# Puls_schaltbild_1_2017.net
KiCad netlist of a schematic drawn in EAGLE
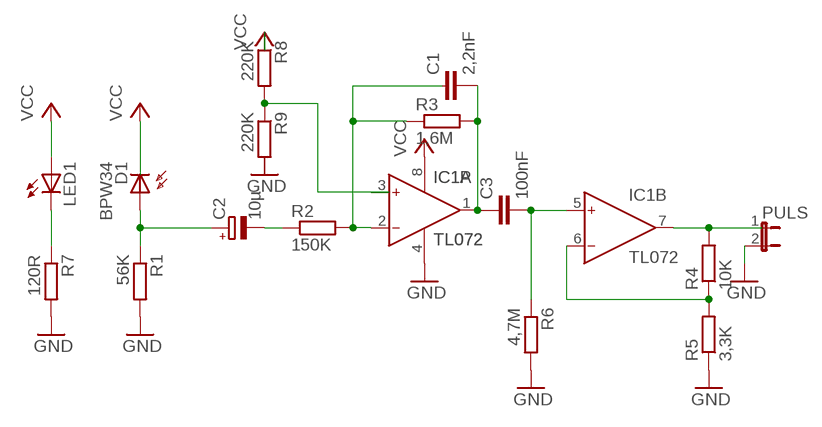
[diagram p0: schematic, sheet 1]

(export (version "E")
  (design (tool "Eeschema 10.0.6"))
  (components
    (comp (ref "C1")
      (value "2,2nF")
      (footprint "eagle-import:C050-024X044")
      (libsource (lib "eagle-import") (part "C-EU050-024X044"))
    )
    (comp (ref "C2")
      (value "10µ")
      (footprint "eagle-import:B45181B")
      (libsource (lib "eagle-import") (part "CPOL-EUB45181B"))
    )
    (comp (ref "C3")
      (value "100nF")
      (footprint "eagle-import:C050-024X044")
      (libsource (lib "eagle-import") (part "C-EU050-024X044"))
    )
    (comp (ref "D1")
      (value "BPW34")
      (footprint "eagle-import:BPW32")
      (libsource (lib "eagle-import") (part "BPW32"))
    )
    (comp (ref "IC1")
      (value "TL072")
      (footprint "eagle-import:DIL08")
      (libsource (lib "eagle-import") (part "AD822N"))
    )
    (comp (ref "LED1")
      (value "LED5MM")
      (footprint "eagle-import:LED5MM")
      (libsource (lib "eagle-import") (part "LED5MM"))
    )
    (comp (ref "PULS")
      (value "JP1E")
      (footprint "eagle-import:JP1")
      (libsource (lib "eagle-import") (part "JP1E"))
    )
    (comp (ref "R1")
      (value "56K")
      (footprint "eagle-import:0207_12")
      (libsource (lib "eagle-import") (part "R-EU_0207/12"))
    )
    (comp (ref "R2")
      (value "150K")
      (footprint "eagle-import:0207_12")
      (libsource (lib "eagle-import") (part "R-EU_0207/12"))
    )
    (comp (ref "R3")
      (value "1,6M")
      (footprint "eagle-import:0207_12")
      (libsource (lib "eagle-import") (part "R-EU_0207/12"))
    )
    (comp (ref "R4")
      (value "10K")
      (footprint "eagle-import:0207_12")
      (libsource (lib "eagle-import") (part "R-EU_0207/12"))
    )
    (comp (ref "R5")
      (value "3,3K")
      (footprint "eagle-import:0207_12")
      (libsource (lib "eagle-import") (part "R-EU_0207/12"))
    )
    (comp (ref "R6")
      (value "4,7M")
      (footprint "eagle-import:0207_12")
      (libsource (lib "eagle-import") (part "R-EU_0207/12"))
    )
    (comp (ref "R7")
      (value "120R")
      (footprint "eagle-import:0207_12")
      (libsource (lib "eagle-import") (part "R-EU_0207/12"))
    )
    (comp (ref "R8")
      (value "220K")
      (footprint "eagle-import:0207_12")
      (libsource (lib "eagle-import") (part "R-EU_0207/12"))
    )
    (comp (ref "R9")
      (value "220K")
      (footprint "eagle-import:0207_12")
      (libsource (lib "eagle-import") (part "R-EU_0207/12"))
    )
  )
  (nets
    (net (code "1") (name "GND") (class "Default")
      (node (ref "IC1") (pin "4") (pinfunction "V-_4") (pintype "power_in"))
      (node (ref "PULS") (pin "2") (pinfunction "2_2") (pintype "passive"))
      (node (ref "R1") (pin "2") (pinfunction "2_2") (pintype "passive"))
      (node (ref "R5") (pin "1") (pinfunction "1_1") (pintype "passive"))
      (node (ref "R6") (pin "2") (pinfunction "2_2") (pintype "passive"))
      (node (ref "R7") (pin "2") (pinfunction "2_2") (pintype "passive"))
    )
    (net (code "2") (name "Net-(C2-Pad+)") (class "Default")
      (node (ref "C2") (pin "+") (pinfunction "+_+") (pintype "passive"))
      (node (ref "D1") (pin "A") (pinfunction "A_A") (pintype "passive"))
      (node (ref "R1") (pin "1") (pinfunction "1_1") (pintype "passive"))
    )
    (net (code "3") (name "Net-(C2-Pad-)") (class "Default")
      (node (ref "C2") (pin "-") (pinfunction "-_-") (pintype "passive"))
      (node (ref "R2") (pin "1") (pinfunction "1_1") (pintype "passive"))
    )
    (net (code "4") (name "Net-(IC1A-IN-)") (class "Default")
      (node (ref "IC1") (pin "2") (pinfunction "IN-_2") (pintype "input"))
      (node (ref "R2") (pin "2") (pinfunction "2_2") (pintype "passive"))
      (node (ref "R3") (pin "1") (pinfunction "1_1") (pintype "passive"))
    )
    (net (code "5") (name "Net-(IC1A-OUT)") (class "Default")
      (node (ref "C1") (pin "2") (pinfunction "2_2") (pintype "passive"))
      (node (ref "C3") (pin "1") (pinfunction "1_1") (pintype "passive"))
      (node (ref "IC1") (pin "1") (pinfunction "OUT_1") (pintype "output"))
      (node (ref "R3") (pin "2") (pinfunction "2_2") (pintype "passive"))
    )
    (net (code "6") (name "Net-(IC1B-IN+)") (class "Default")
      (node (ref "C3") (pin "2") (pinfunction "2_2") (pintype "passive"))
      (node (ref "IC1") (pin "5") (pinfunction "IN+_5") (pintype "input"))
      (node (ref "R6") (pin "1") (pinfunction "1_1") (pintype "passive"))
    )
    (net (code "7") (name "Net-(IC1B-IN-)") (class "Default")
      (node (ref "IC1") (pin "6") (pinfunction "IN-_6") (pintype "input"))
      (node (ref "R4") (pin "1") (pinfunction "1_1") (pintype "passive"))
      (node (ref "R5") (pin "2") (pinfunction "2_2") (pintype "passive"))
    )
    (net (code "8") (name "Net-(IC1B-OUT)") (class "Default")
      (node (ref "IC1") (pin "7") (pinfunction "OUT_7") (pintype "output"))
      (node (ref "R4") (pin "2") (pinfunction "2_2") (pintype "passive"))
    )
    (net (code "9") (name "Net-(LED1-C)") (class "Default")
      (node (ref "LED1") (pin "K") (pinfunction "C_K") (pintype "passive"))
      (node (ref "R7") (pin "1") (pinfunction "1_1") (pintype "passive"))
    )
    (net (code "10") (name "Net-(R8-Pad2)") (class "Default")
      (node (ref "R8") (pin "2") (pinfunction "2_2") (pintype "passive"))
      (node (ref "R9") (pin "1") (pinfunction "1_1") (pintype "passive"))
    )
    (net (code "11") (name "VCC") (class "Default")
      (node (ref "IC1") (pin "8") (pinfunction "V+_8") (pintype "power_in"))
      (node (ref "LED1") (pin "A") (pinfunction "A_A") (pintype "passive"))
      (node (ref "R8") (pin "1") (pinfunction "1_1") (pintype "passive"))
    )
    (net (code "12") (name "unconnected-(C1-Pad1)") (class "Default")
      (node (ref "C1") (pin "1") (pinfunction "1_1") (pintype "passive"))
    )
    (net (code "13") (name "unconnected-(D1-C-PadK)") (class "Default")
      (node (ref "D1") (pin "K") (pinfunction "C_K") (pintype "passive"))
    )
    (net (code "14") (name "unconnected-(IC1A-IN+-Pad3)") (class "Default")
      (node (ref "IC1") (pin "3") (pinfunction "IN+_3") (pintype "input"))
    )
    (net (code "15") (name "unconnected-(PULS-Pad1)") (class "Default")
      (node (ref "PULS") (pin "1") (pinfunction "1_1") (pintype "passive"))
    )
    (net (code "16") (name "unconnected-(R9-Pad2)") (class "Default")
      (node (ref "R9") (pin "2") (pinfunction "2_2") (pintype "passive"))
    )
  )
)
